# ALIM_MOSFET.net
KiCad netlist of a schematic drawn in Altium Designer
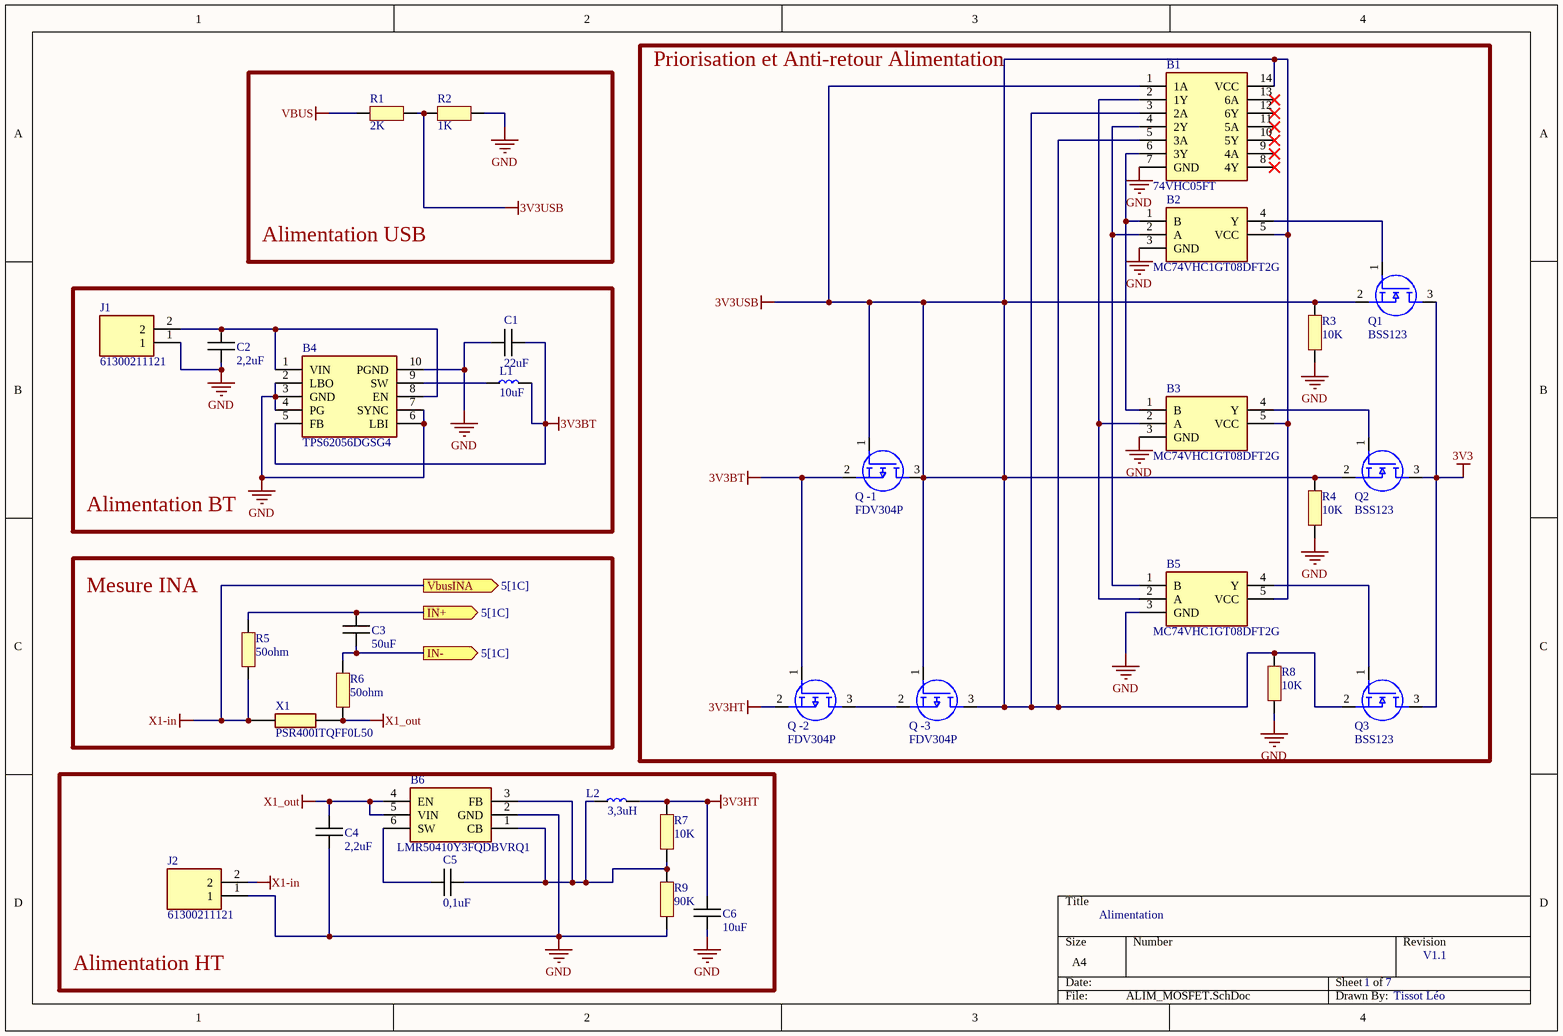
[diagram p0: ALIM_MOSFET.SchDoc]

(export (version "E")
  (design (tool "Eeschema 10.0.6"))
  (components
    (comp (ref "B1")
      (value "74VHC05FT")
      (footprint "SOP65P640X120-14N")
      (description "Logic Gates CMOS LOGIC IC INVERTER")
      (fields (field (name "MOUSER PART NUMBER") "757-74VHC05FT"))
      (libsource (lib "SCHLibrary") (part "74VHC05FT"))
    )
    (comp (ref "B2")
      (value "MC74VHC1GT08DFT2G")
      (footprint "SOT65P210X110-5N")
      (description "Single 2-Input AND Gate, TTL Level")
      (libsource (lib "SCHLibrary") (part "MC74VHC1GT08DFT2G"))
    )
    (comp (ref "B3")
      (value "MC74VHC1GT08DFT2G")
      (footprint "SOT65P210X110-5N")
      (description "Single 2-Input AND Gate, TTL Level")
      (libsource (lib "SCHLibrary") (part "MC74VHC1GT08DFT2G"))
    )
    (comp (ref "B4")
      (value "TPS62056DGSG4")
      (footprint "SOP50P490X110-10N")
      (fields (field (name "MOUSER PART NUMBER") "595-TPS62056DGSG4"))
      (libsource (lib "SCHLibrary") (part "TPS62056DGSG4"))
    )
    (comp (ref "B5")
      (value "MC74VHC1GT08DFT2G")
      (footprint "SOT65P210X110-5N")
      (description "Single 2-Input AND Gate, TTL Level")
      (libsource (lib "SCHLibrary") (part "MC74VHC1GT08DFT2G"))
    )
    (comp (ref "B6")
      (value "LMR50410Y3FQDBVRQ1")
      (footprint "SOT95P280X145-6N")
      (fields (field (name "MOUSER PART NUMBER") "595-R50410Y3FQDBVRQ1"))
      (libsource (lib "SCHLibrary") (part "LMR50410Y3FQDBVRQ1"))
    )
    (comp (ref "C1")
      (value "22uF")
      (footprint "CAPC1005X06N")
      (libsource (lib "SCHLibrary") (part "Capacitor"))
    )
    (comp (ref "C2")
      (value "2,2uF")
      (footprint "CAPC1005X06N")
      (libsource (lib "SCHLibrary") (part "Capacitor"))
    )
    (comp (ref "C3")
      (value "50uF")
      (footprint "CAPC1005X06N")
      (libsource (lib "SCHLibrary") (part "Capacitor"))
    )
    (comp (ref "C4")
      (value "2,2uF")
      (footprint "CAPC1005X06N")
      (libsource (lib "SCHLibrary") (part "Capacitor"))
    )
    (comp (ref "C5")
      (value "0,1uF")
      (footprint "CAPC1005X06N")
      (libsource (lib "SCHLibrary") (part "Capacitor"))
    )
    (comp (ref "C6")
      (value "10uF")
      (footprint "CAPC1005X06N")
      (libsource (lib "SCHLibrary") (part "Capacitor"))
    )
    (comp (ref "J1")
      (value "61300211121")
      (footprint "61300211121")
      (description "WURTH ELEKTRONIK - 61300211121 - HEADER, 2.54MM, PIN, THT, VERTICAL, 2WAY")
      (libsource (lib "SCHLibrary") (part "61300211121"))
    )
    (comp (ref "J2")
      (value "61300211121")
      (footprint "61300211121")
      (description "WURTH ELEKTRONIK - 61300211121 - HEADER, 2.54MM, PIN, THT, VERTICAL, 2WAY")
      (libsource (lib "SCHLibrary") (part "61300211121"))
    )
    (comp (ref "L1") (value "10uF") (footprint "LQPC1005X06N") (libsource (lib "SCHLibrary") (part "Bobine")))
    (comp (ref "L2")
      (value "3,3uH")
      (footprint "LQPC1005X06N")
      (libsource (lib "SCHLibrary") (part "Bobine"))
    )
    (comp (ref "Q -1")
      (value "FDV304P")
      (footprint "SOT95P251X112-3N")
      (fields (field (name "MOUSER PART NUMBER") "512-FDV304P"))
      (libsource (lib "SCHLibrary") (part "FDV304P"))
    )
    (comp (ref "Q -2")
      (value "FDV304P")
      (footprint "SOT95P251X112-3N")
      (fields (field (name "MOUSER PART NUMBER") "512-FDV304P"))
      (libsource (lib "SCHLibrary") (part "FDV304P"))
    )
    (comp (ref "Q -3")
      (value "FDV304P")
      (footprint "SOT95P251X112-3N")
      (fields (field (name "MOUSER PART NUMBER") "512-FDV304P"))
      (libsource (lib "SCHLibrary") (part "FDV304P"))
    )
    (comp (ref "Q1")
      (value "BSS123")
      (footprint "BSS123")
      (description "BSS123 N-Channel MOSFET, 170 mA, 100 V PowerTrench, 3-Pin SOT-23 ON Semiconductor")
      (libsource (lib "SCHLibrary") (part "BSS123"))
    )
    (comp (ref "Q2")
      (value "BSS123")
      (footprint "BSS123")
      (description "BSS123 N-Channel MOSFET, 170 mA, 100 V PowerTrench, 3-Pin SOT-23 ON Semiconductor")
      (libsource (lib "SCHLibrary") (part "BSS123"))
    )
    (comp (ref "Q3")
      (value "BSS123")
      (footprint "BSS123")
      (description "BSS123 N-Channel MOSFET, 170 mA, 100 V PowerTrench, 3-Pin SOT-23 ON Semiconductor")
      (libsource (lib "SCHLibrary") (part "BSS123"))
    )
    (comp (ref "R1") (value "2K") (footprint "RESC1005X06N") (libsource (lib "SCHLibrary") (part "Resistor")))
    (comp (ref "R2") (value "1K") (footprint "RESC1005X06N") (libsource (lib "SCHLibrary") (part "Resistor")))
    (comp (ref "R3") (value "10K") (footprint "RESC1005X06N") (libsource (lib "") (part "Resistor_1")))
    (comp (ref "R4") (value "10K") (footprint "RESC1005X06N") (libsource (lib "") (part "Resistor_1")))
    (comp (ref "R5") (value "50ohm") (footprint "RESC1005X06N") (libsource (lib "") (part "Resistor_2")))
    (comp (ref "R6") (value "50ohm") (footprint "RESC1005X06N") (libsource (lib "") (part "Resistor_2")))
    (comp (ref "R7") (value "10K") (footprint "RESC1005X06N") (libsource (lib "") (part "Resistor_1")))
    (comp (ref "R8") (value "10K") (footprint "RESC1005X06N") (libsource (lib "") (part "Resistor_1")))
    (comp (ref "R9") (value "90K") (footprint "RESC1005X06N") (libsource (lib "") (part "Resistor_1")))
    (comp (ref "X1")
      (value "PSR400ITQFF0L50")
      (footprint "RESC10052X200N")
      (fields (field (name "MOUSER PART NUMBER") "755-PSR400ITQFF0L50"))
      (libsource (lib "SCHLibrary") (part "PSR400ITQFF0L50"))
    )
  )
  (nets
    (net (code "1") (name "/IN+") (class "Default")
      (node (ref "C3") (pin "1") (pinfunction "1_1") (pintype "passive"))
      (node (ref "R5") (pin "2") (pinfunction "2_2") (pintype "passive"))
    )
    (net (code "2") (name "/IN-") (class "Default")
      (node (ref "C3") (pin "2") (pinfunction "2_2") (pintype "passive"))
      (node (ref "R6") (pin "2") (pinfunction "2_2") (pintype "passive"))
    )
    (net (code "3") (name "3V3") (class "Default")
      (node (ref "Q1") (pin "3") (pinfunction "D_3") (pintype "passive"))
      (node (ref "Q2") (pin "3") (pinfunction "D_3") (pintype "passive"))
      (node (ref "Q3") (pin "3") (pinfunction "D_3") (pintype "passive"))
    )
    (net (code "4") (name "3V3BT") (class "Default")
      (node (ref "B4") (pin "5") (pinfunction "FB_5") (pintype "passive"))
      (node (ref "C1") (pin "1") (pinfunction "1_1") (pintype "passive"))
      (node (ref "L1") (pin "2") (pinfunction "2_2") (pintype "passive"))
      (node (ref "Q -1") (pin "2") (pinfunction "S_2") (pintype "passive"))
      (node (ref "Q -2") (pin "1") (pinfunction "G_1") (pintype "passive"))
    )
    (net (code "5") (name "3V3HT") (class "Default")
      (node (ref "C6") (pin "1") (pinfunction "1_1") (pintype "passive"))
      (node (ref "L2") (pin "2") (pinfunction "2_2") (pintype "passive"))
      (node (ref "Q -2") (pin "2") (pinfunction "S_2") (pintype "passive"))
      (node (ref "R7") (pin "1") (pinfunction "1_1") (pintype "passive"))
    )
    (net (code "6") (name "3V3USB") (class "Default")
      (node (ref "B1") (pin "1") (pinfunction "1A_1") (pintype "passive"))
      (node (ref "B1") (pin "14") (pinfunction "VCC_14") (pintype "passive"))
      (node (ref "B1") (pin "3") (pinfunction "2A_3") (pintype "passive"))
      (node (ref "B1") (pin "5") (pinfunction "3A_5") (pintype "passive"))
      (node (ref "B2") (pin "5") (pinfunction "VCC_5") (pintype "passive"))
      (node (ref "B3") (pin "5") (pinfunction "VCC_5") (pintype "passive"))
      (node (ref "B5") (pin "5") (pinfunction "VCC_5") (pintype "passive"))
      (node (ref "Q -1") (pin "1") (pinfunction "G_1") (pintype "passive"))
      (node (ref "Q -1") (pin "3") (pinfunction "D_3") (pintype "passive"))
      (node (ref "Q -3") (pin "1") (pinfunction "G_1") (pintype "passive"))
      (node (ref "Q -3") (pin "3") (pinfunction "D_3") (pintype "passive"))
      (node (ref "Q1") (pin "2") (pinfunction "S_2") (pintype "passive"))
      (node (ref "Q2") (pin "2") (pinfunction "S_2") (pintype "passive"))
      (node (ref "Q3") (pin "2") (pinfunction "S_2") (pintype "passive"))
      (node (ref "R1") (pin "2") (pinfunction "2_2") (pintype "passive"))
      (node (ref "R2") (pin "1") (pinfunction "1_1") (pintype "passive"))
      (node (ref "R3") (pin "1") (pinfunction "1_1") (pintype "passive"))
      (node (ref "R4") (pin "1") (pinfunction "1_1") (pintype "passive"))
      (node (ref "R8") (pin "1") (pinfunction "1_1") (pintype "passive"))
    )
    (net (code "7") (name "GND") (class "Default")
      (node (ref "B1") (pin "7") (pinfunction "GND_7") (pintype "passive"))
      (node (ref "B2") (pin "3") (pinfunction "GND_3") (pintype "passive"))
      (node (ref "B3") (pin "3") (pinfunction "GND_3") (pintype "passive"))
      (node (ref "B4") (pin "10") (pinfunction "PGND_10") (pintype "passive"))
      (node (ref "B4") (pin "2") (pinfunction "LBO_2") (pintype "passive"))
      (node (ref "B4") (pin "3") (pinfunction "GND_3") (pintype "passive"))
      (node (ref "B4") (pin "4") (pinfunction "PG_4") (pintype "passive"))
      (node (ref "B4") (pin "6") (pinfunction "LBI_6") (pintype "passive"))
      (node (ref "B4") (pin "7") (pinfunction "SYNC_7") (pintype "passive"))
      (node (ref "B5") (pin "3") (pinfunction "GND_3") (pintype "passive"))
      (node (ref "B6") (pin "2") (pinfunction "GND_2") (pintype "passive"))
      (node (ref "C1") (pin "2") (pinfunction "2_2") (pintype "passive"))
      (node (ref "C2") (pin "2") (pinfunction "2_2") (pintype "passive"))
      (node (ref "C4") (pin "2") (pinfunction "2_2") (pintype "passive"))
      (node (ref "C6") (pin "2") (pinfunction "2_2") (pintype "passive"))
      (node (ref "J1") (pin "1") (pinfunction "1_1") (pintype "passive"))
      (node (ref "J2") (pin "1") (pinfunction "1_1") (pintype "passive"))
      (node (ref "R2") (pin "2") (pinfunction "2_2") (pintype "passive"))
      (node (ref "R3") (pin "2") (pinfunction "2_2") (pintype "passive"))
      (node (ref "R4") (pin "2") (pinfunction "2_2") (pintype "passive"))
      (node (ref "R8") (pin "2") (pinfunction "2_2") (pintype "passive"))
      (node (ref "R9") (pin "2") (pinfunction "2_2") (pintype "passive"))
    )
    (net (code "8") (name "Net-(B1-1Y)") (class "Default")
      (node (ref "B1") (pin "2") (pinfunction "1Y_2") (pintype "passive"))
      (node (ref "B3") (pin "2") (pinfunction "A_2") (pintype "passive"))
      (node (ref "B5") (pin "2") (pinfunction "A_2") (pintype "passive"))
    )
    (net (code "9") (name "Net-(B1-2Y)") (class "Default")
      (node (ref "B1") (pin "4") (pinfunction "2Y_4") (pintype "passive"))
      (node (ref "B2") (pin "2") (pinfunction "A_2") (pintype "passive"))
      (node (ref "B5") (pin "1") (pinfunction "B_1") (pintype "passive"))
    )
    (net (code "10") (name "Net-(B1-3Y)") (class "Default")
      (node (ref "B1") (pin "6") (pinfunction "3Y_6") (pintype "passive"))
      (node (ref "B2") (pin "1") (pinfunction "B_1") (pintype "passive"))
      (node (ref "B3") (pin "1") (pinfunction "B_1") (pintype "passive"))
    )
    (net (code "11") (name "Net-(B2-Y)") (class "Default")
      (node (ref "B2") (pin "4") (pinfunction "Y_4") (pintype "passive"))
      (node (ref "Q1") (pin "1") (pinfunction "G_1") (pintype "passive"))
    )
    (net (code "12") (name "Net-(B3-Y)") (class "Default")
      (node (ref "B3") (pin "4") (pinfunction "Y_4") (pintype "passive"))
      (node (ref "Q2") (pin "1") (pinfunction "G_1") (pintype "passive"))
    )
    (net (code "13") (name "Net-(B4-EN)") (class "Default")
      (node (ref "B4") (pin "1") (pinfunction "VIN_1") (pintype "passive"))
      (node (ref "B4") (pin "8") (pinfunction "EN_8") (pintype "passive"))
      (node (ref "C2") (pin "1") (pinfunction "1_1") (pintype "passive"))
      (node (ref "J1") (pin "2") (pinfunction "2_2") (pintype "passive"))
    )
    (net (code "14") (name "Net-(B4-SW)") (class "Default")
      (node (ref "B4") (pin "9") (pinfunction "SW_9") (pintype "passive"))
      (node (ref "L1") (pin "1") (pinfunction "1_1") (pintype "passive"))
    )
    (net (code "15") (name "Net-(B5-Y)") (class "Default")
      (node (ref "B5") (pin "4") (pinfunction "Y_4") (pintype "passive"))
      (node (ref "Q3") (pin "1") (pinfunction "G_1") (pintype "passive"))
    )
    (net (code "16") (name "Net-(B6-CB)") (class "Default")
      (node (ref "B6") (pin "1") (pinfunction "CB_1") (pintype "passive"))
      (node (ref "B6") (pin "3") (pinfunction "FB_3") (pintype "passive"))
      (node (ref "C5") (pin "1") (pinfunction "1_1") (pintype "passive"))
      (node (ref "L2") (pin "1") (pinfunction "1_1") (pintype "passive"))
      (node (ref "R7") (pin "2") (pinfunction "2_2") (pintype "passive"))
      (node (ref "R9") (pin "1") (pinfunction "1_1") (pintype "passive"))
    )
    (net (code "17") (name "Net-(B6-SW)") (class "Default")
      (node (ref "B6") (pin "6") (pinfunction "SW_6") (pintype "passive"))
      (node (ref "C5") (pin "2") (pinfunction "2_2") (pintype "passive"))
    )
    (net (code "18") (name "Net-(Q -2-D)") (class "Default")
      (node (ref "Q -2") (pin "3") (pinfunction "D_3") (pintype "passive"))
      (node (ref "Q -3") (pin "2") (pinfunction "S_2") (pintype "passive"))
    )
    (net (code "19") (name "VBUS") (class "Default")
      (node (ref "R1") (pin "1") (pinfunction "1_1") (pintype "passive"))
    )
    (net (code "20") (name "X1-in") (class "Default")
      (node (ref "J2") (pin "2") (pinfunction "2_2") (pintype "passive"))
      (node (ref "R5") (pin "1") (pinfunction "1_1") (pintype "passive"))
      (node (ref "X1") (pin "1") (pinfunction "1_1") (pintype "passive"))
    )
    (net (code "21") (name "X1_out") (class "Default")
      (node (ref "B6") (pin "4") (pinfunction "EN_4") (pintype "passive"))
      (node (ref "B6") (pin "5") (pinfunction "VIN_5") (pintype "passive"))
      (node (ref "C4") (pin "1") (pinfunction "1_1") (pintype "passive"))
      (node (ref "R6") (pin "1") (pinfunction "1_1") (pintype "passive"))
      (node (ref "X1") (pin "2") (pinfunction "2_2") (pintype "passive"))
    )
    (net (code "22") (name "unconnected-(B1-4A-Pad9)") (class "Default")
      (node (ref "B1") (pin "9") (pinfunction "4A_9") (pintype "passive+no_connect"))
    )
    (net (code "23") (name "unconnected-(B1-4Y-Pad8)") (class "Default")
      (node (ref "B1") (pin "8") (pinfunction "4Y_8") (pintype "passive+no_connect"))
    )
    (net (code "24") (name "unconnected-(B1-5A-Pad11)") (class "Default")
      (node (ref "B1") (pin "11") (pinfunction "5A_11") (pintype "passive+no_connect"))
    )
    (net (code "25") (name "unconnected-(B1-5Y-Pad10)") (class "Default")
      (node (ref "B1") (pin "10") (pinfunction "5Y_10") (pintype "passive+no_connect"))
    )
    (net (code "26") (name "unconnected-(B1-6A-Pad13)") (class "Default")
      (node (ref "B1") (pin "13") (pinfunction "6A_13") (pintype "passive+no_connect"))
    )
    (net (code "27") (name "unconnected-(B1-6Y-Pad12)") (class "Default")
      (node (ref "B1") (pin "12") (pinfunction "6Y_12") (pintype "passive+no_connect"))
    )
  )
)
